# Sheet2.net
KiCad netlist of a schematic drawn in Altium Designer
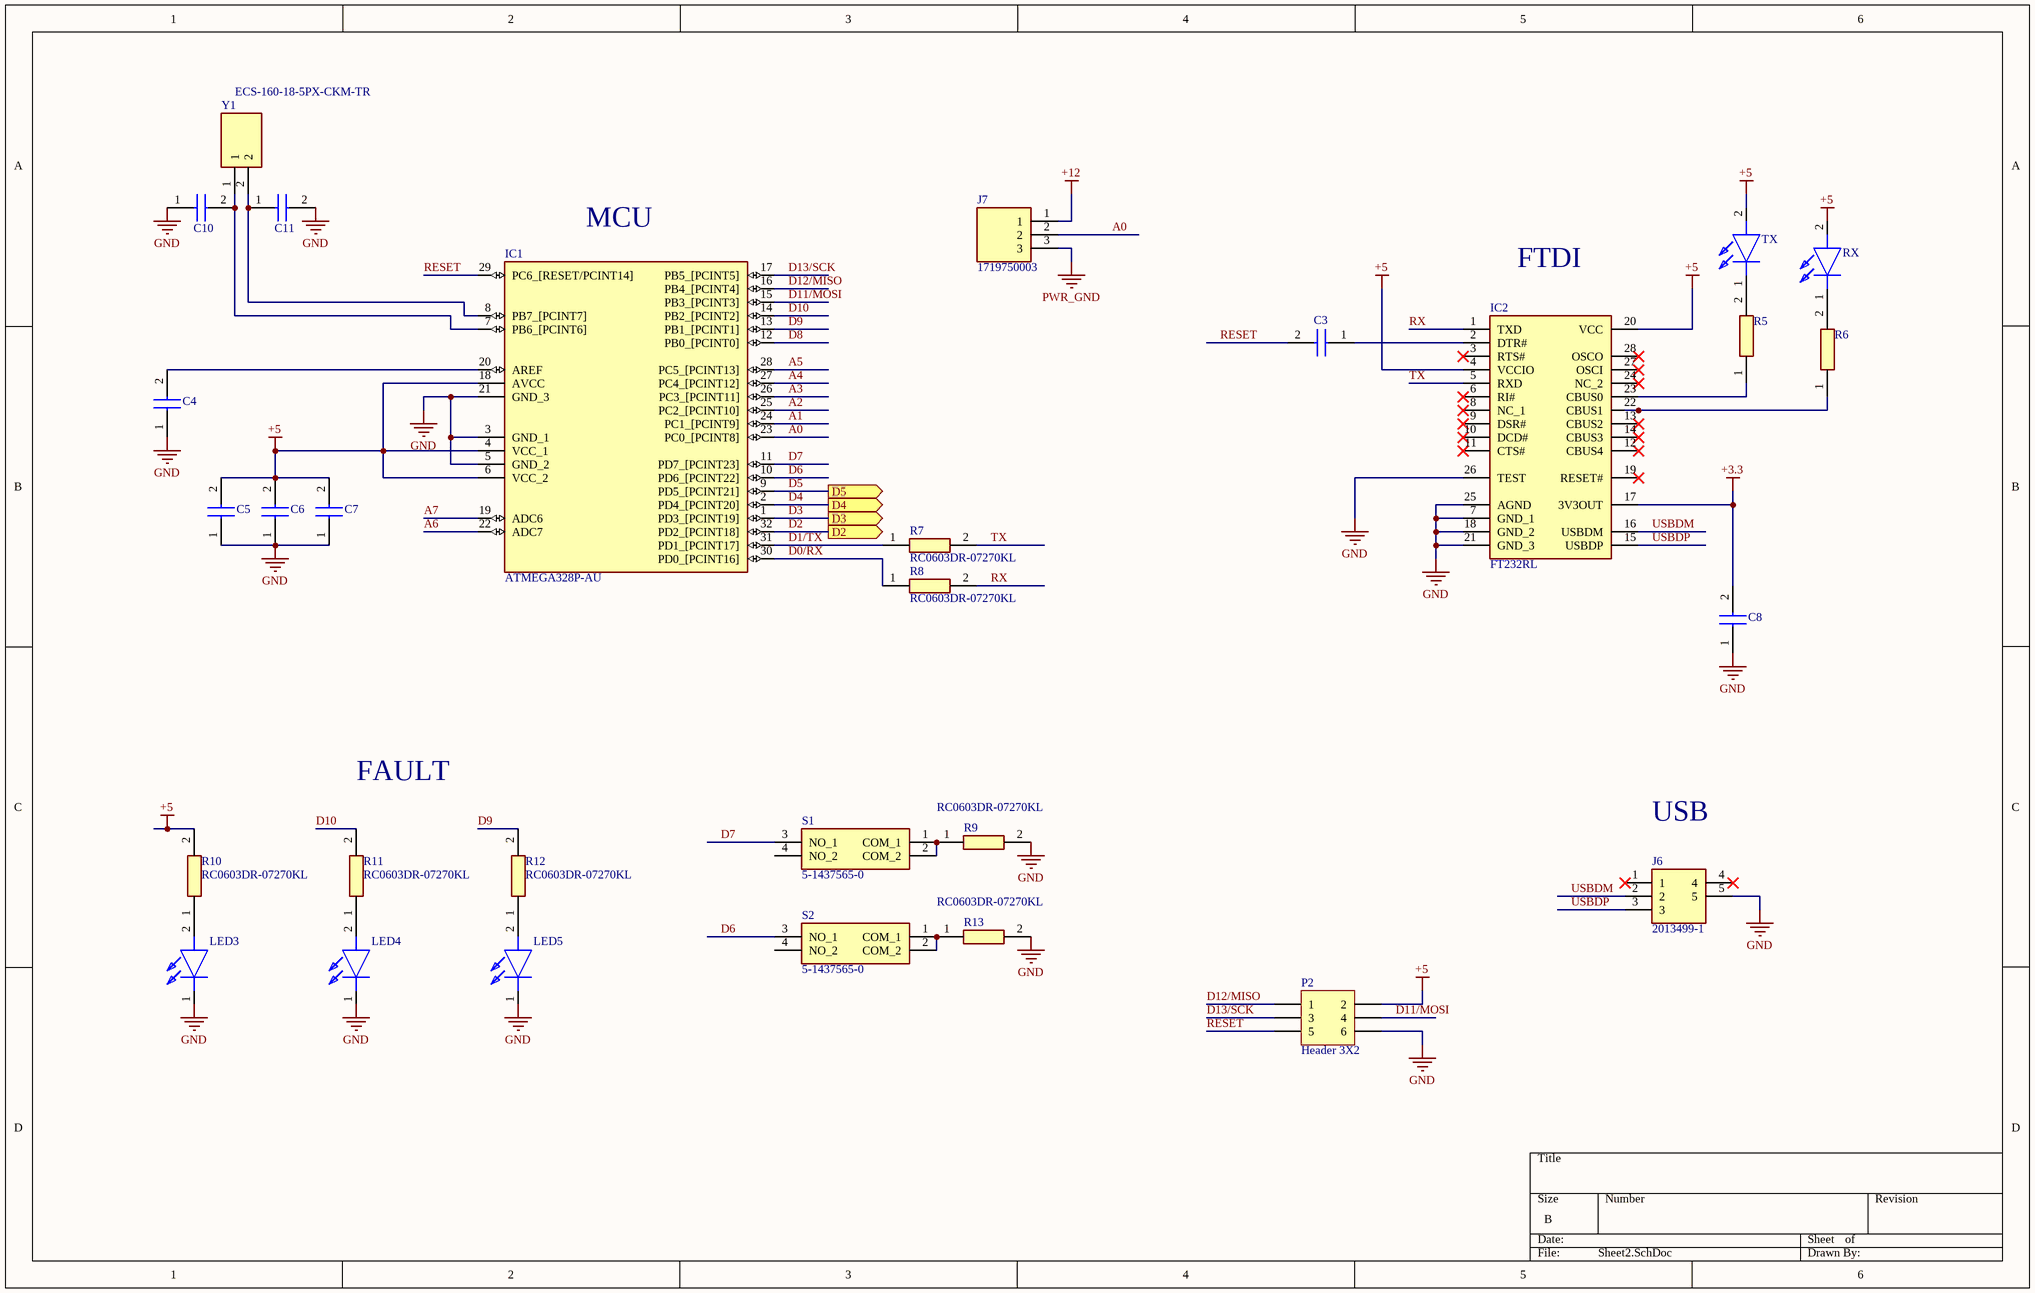
[diagram p0: Sheet2.SchDoc]

(export (version "E")
  (design (tool "Eeschema 10.0.6"))
  (components
    (comp (ref "C3")
      (value "C0603C104K3RACTU")
      (footprint "SamacSys:CAPC1608X95N")
      (description "Capacitor")
      (fields (field (name "MOUSER PART NUMBER") "80-C0603C104K3R"))
      (libsource (lib "PCB_Project") (part "C0603C104K3RACTU"))
    )
    (comp (ref "C4")
      (value "C0603C104K3RACTU")
      (footprint "SamacSys:CAPC1608X95N")
      (description "Capacitor")
      (fields (field (name "MOUSER PART NUMBER") "80-C0603C104K3R"))
      (libsource (lib "PCB_Project") (part "C0603C104K3RACTU"))
    )
    (comp (ref "C5")
      (value "C0603C104K3RACTU")
      (footprint "SamacSys:CAPC1608X95N")
      (description "Capacitor")
      (fields (field (name "MOUSER PART NUMBER") "80-C0603C104K3R"))
      (libsource (lib "PCB_Project") (part "C0603C104K3RACTU"))
    )
    (comp (ref "C6")
      (value "C0603C104K3RACTU")
      (footprint "SamacSys:CAPC1608X95N")
      (description "Capacitor")
      (fields (field (name "MOUSER PART NUMBER") "80-C0603C104K3R"))
      (libsource (lib "PCB_Project") (part "C0603C104K3RACTU"))
    )
    (comp (ref "C7")
      (value "C0603C104K3RACTU")
      (footprint "SamacSys:CAPC1608X95N")
      (description "Capacitor")
      (fields (field (name "MOUSER PART NUMBER") "80-C0603C104K3R"))
      (libsource (lib "PCB_Project") (part "C0603C104K3RACTU"))
    )
    (comp (ref "C8")
      (value "C0603C104K3RACTU")
      (footprint "SamacSys:CAPC1608X95N")
      (description "Capacitor")
      (fields (field (name "MOUSER PART NUMBER") "80-C0603C104K3R"))
      (libsource (lib "PCB_Project") (part "C0603C104K3RACTU"))
    )
    (comp (ref "C10")
      (value "C0603C104K3RACTU")
      (footprint "CAPC1608X95N")
      (description "Capacitor 20pf")
      (fields (field (name "MOUSER PART NUMBER") "80-C0603C104K3R"))
      (libsource (lib "PCB_Project") (part "06035A200KAT2A"))
    )
    (comp (ref "C11")
      (value "C0603C104K3RACTU")
      (footprint "CAPC1608X95N")
      (description "Capacitor 20pf")
      (fields (field (name "MOUSER PART NUMBER") "80-C0603C104K3R"))
      (libsource (lib "PCB_Project") (part "06035A200KAT2A"))
    )
    (comp (ref "IC1")
      (value "ATMEGA328P-AU")
      (footprint "SamacSys:QFP80P900X900X120-32N")
      (description "Integrated Circuit")
      (fields (field (name "MOUSER PART NUMBER") "556-ATMEGA328P-AU"))
      (libsource (lib "PCB_Project") (part "ATMEGA328P-AU"))
    )
    (comp (ref "IC2")
      (value "FT232RL")
      (footprint "SamacSys:SOP65P778X200-28N")
      (description "Integrated Circuit")
      (libsource (lib "PCB_Project") (part "FT232RL"))
    )
    (comp (ref "J6")
      (value "2013499-1")
      (footprint "SamacSys:2013499-1")
      (description "Connector")
      (fields (field (name "MOUSER PART NUMBER") "571-2013499-1"))
      (libsource (lib "*") (part "2013499-1"))
    )
    (comp (ref "J7")
      (value "1719750003")
      (footprint "171975YY03")
      (description "Connector")
      (libsource (lib "PCB_Project") (part "1719750003"))
    )
    (comp (ref "LED3")
      (value "LTST-C191TBKT-5A")
      (footprint "SamacSys:LEDC1608X65N")
      (description "LED")
      (fields (field (name "MOUSER PART NUMBER") "859-LTST-C191TBKT-5A"))
      (libsource (lib "*") (part "LTST-C191TBKT-5A"))
    )
    (comp (ref "LED4")
      (value "LTST-C191TBKT-5A")
      (footprint "SamacSys:LEDC1608X65N")
      (description "LED")
      (fields (field (name "MOUSER PART NUMBER") "859-LTST-C191TBKT-5A"))
      (libsource (lib "*") (part "LTST-C191TBKT-5A"))
    )
    (comp (ref "LED5")
      (value "LTST-C191TBKT-5A")
      (footprint "SamacSys:LEDC1608X65N")
      (description "LED")
      (fields (field (name "MOUSER PART NUMBER") "859-LTST-C191TBKT-5A"))
      (libsource (lib "*") (part "LTST-C191TBKT-5A"))
    )
    (comp (ref "P2")
      (value "Header 3X2")
      (footprint "HDR2X3")
      (description "Header, 3-Pin, Dual row")
      (fields (field (name "PUBLISHER") "Altium Limited"))
      (libsource (lib "Miscellaneous Connectors") (part "Header 3X2"))
    )
    (comp (ref "R5")
      (value "RC0603DR-07270KL")
      (footprint "SamacSys:RESC1608X55N")
      (description "Resistor")
      (libsource (lib "PCB_Project") (part "RC0603DR-07270KL"))
    )
    (comp (ref "R6")
      (value "RC0603DR-07270KL")
      (footprint "SamacSys:RESC1608X55N")
      (description "Resistor")
      (libsource (lib "PCB_Project") (part "RC0603DR-07270KL"))
    )
    (comp (ref "R7")
      (value "RC0603DR-07270KL")
      (footprint "SamacSys:RESC1608X55N")
      (description "Resistor")
      (libsource (lib "") (part "RC0603DR-07270KL_1"))
    )
    (comp (ref "R8")
      (value "RC0603DR-07270KL")
      (footprint "SamacSys:RESC1608X55N")
      (description "Resistor")
      (libsource (lib "") (part "RC0603DR-07270KL_1"))
    )
    (comp (ref "R9")
      (value "RC0603DR-07270KL")
      (footprint "SamacSys:RESC1608X55N")
      (description "Resistor")
      (libsource (lib "") (part "RC0603DR-07270KL_1"))
    )
    (comp (ref "R10")
      (value "RC0603DR-07270KL")
      (footprint "SamacSys:RESC1608X55N")
      (description "Resistor")
      (libsource (lib "PCB_Project") (part "RC0603DR-07270KL"))
    )
    (comp (ref "R11")
      (value "RC0603DR-07270KL")
      (footprint "SamacSys:RESC1608X55N")
      (description "Resistor")
      (libsource (lib "PCB_Project") (part "RC0603DR-07270KL"))
    )
    (comp (ref "R12")
      (value "RC0603DR-07270KL")
      (footprint "SamacSys:RESC1608X55N")
      (description "Resistor")
      (libsource (lib "PCB_Project") (part "RC0603DR-07270KL"))
    )
    (comp (ref "R13")
      (value "RC0603DR-07270KL")
      (footprint "SamacSys:RESC1608X55N")
      (description "Resistor")
      (libsource (lib "") (part "RC0603DR-07270KL_1"))
    )
    (comp (ref "RX")
      (value "LTST-C191TBKT-5A")
      (footprint "SamacSys:LEDC1608X65N")
      (description "LED")
      (fields (field (name "MOUSER PART NUMBER") "859-LTST-C191TBKT-5A"))
      (libsource (lib "*") (part "LTST-C191TBKT-5A"))
    )
    (comp (ref "S1")
      (value "5-1437565-0")
      (footprint "SamacSys:FSM6JSMATR")
      (description "Switch")
      (fields (field (name "MOUSER PART NUMBER") "506-5-1437565-0"))
      (libsource (lib "*") (part "5-1437565-0"))
    )
    (comp (ref "S2")
      (value "5-1437565-0")
      (footprint "SamacSys:FSM6JSMATR")
      (description "Switch")
      (fields (field (name "MOUSER PART NUMBER") "506-5-1437565-0"))
      (libsource (lib "*") (part "5-1437565-0"))
    )
    (comp (ref "TX")
      (value "LTST-C191TBKT-5A")
      (footprint "SamacSys:LEDC1608X65N")
      (description "LED")
      (fields (field (name "MOUSER PART NUMBER") "859-LTST-C191TBKT-5A"))
      (libsource (lib "*") (part "LTST-C191TBKT-5A"))
    )
    (comp (ref "Y1")
      (value "ECS-160-18-5PX-CKM-TR")
      (footprint "ECS49205PXTR")
      (description "Crystal or Oscillator")
      (libsource (lib "PCB_Project") (part "ECS-160-18-5PX-CKM-TR"))
    )
  )
  (nets
    (net (code "1") (name "+3.3") (class "Default")
      (node (ref "C8") (pin "2") (pinfunction "2_2") (pintype "passive"))
      (node (ref "IC2") (pin "17") (pinfunction "3V3OUT_17") (pintype "passive"))
    )
    (net (code "2") (name "+5") (class "Default")
      (node (ref "C5") (pin "2") (pinfunction "2_2") (pintype "passive"))
      (node (ref "C6") (pin "2") (pinfunction "2_2") (pintype "passive"))
      (node (ref "C7") (pin "2") (pinfunction "2_2") (pintype "passive"))
      (node (ref "IC1") (pin "18") (pinfunction "AVCC_18") (pintype "power_in"))
      (node (ref "IC1") (pin "4") (pinfunction "VCC_1_4") (pintype "power_in"))
      (node (ref "IC1") (pin "6") (pinfunction "VCC_2_6") (pintype "power_in"))
      (node (ref "IC2") (pin "20") (pinfunction "VCC_20") (pintype "passive"))
      (node (ref "IC2") (pin "4") (pinfunction "VCCIO_4") (pintype "passive"))
      (node (ref "P2") (pin "2") (pinfunction "2_2") (pintype "passive"))
      (node (ref "R10") (pin "2") (pinfunction "2_2") (pintype "passive"))
      (node (ref "RX") (pin "2") (pinfunction "A_2") (pintype "passive"))
      (node (ref "TX") (pin "2") (pinfunction "A_2") (pintype "passive"))
    )
    (net (code "3") (name "+12") (class "Default")
      (node (ref "J7") (pin "1") (pinfunction "1_1") (pintype "passive"))
    )
    (net (code "4") (name "/A0") (class "Default")
      (node (ref "IC1") (pin "23") (pinfunction "PC0_[PCINT8]_23") (pintype "bidirectional"))
      (node (ref "J7") (pin "2") (pinfunction "2_2") (pintype "passive"))
    )
    (net (code "5") (name "/A1") (class "Default")
      (node (ref "IC1") (pin "24") (pinfunction "PC1_[PCINT9]_24") (pintype "bidirectional"))
    )
    (net (code "6") (name "/A2") (class "Default")
      (node (ref "IC1") (pin "25") (pinfunction "PC2_[PCINT10]_25") (pintype "bidirectional"))
    )
    (net (code "7") (name "/A3") (class "Default")
      (node (ref "IC1") (pin "26") (pinfunction "PC3_[PCINT11]_26") (pintype "bidirectional"))
    )
    (net (code "8") (name "/A4") (class "Default")
      (node (ref "IC1") (pin "27") (pinfunction "PC4_[PCINT12]_27") (pintype "bidirectional"))
    )
    (net (code "9") (name "/A5") (class "Default")
      (node (ref "IC1") (pin "28") (pinfunction "PC5_[PCINT13]_28") (pintype "bidirectional"))
    )
    (net (code "10") (name "/A6") (class "Default")
      (node (ref "IC1") (pin "22") (pinfunction "ADC7_22") (pintype "bidirectional"))
    )
    (net (code "11") (name "/A7") (class "Default")
      (node (ref "IC1") (pin "19") (pinfunction "ADC6_19") (pintype "bidirectional"))
    )
    (net (code "12") (name "/D0{slash}RX") (class "Default")
      (node (ref "IC1") (pin "30") (pinfunction "PD0_[PCINT16]_30") (pintype "bidirectional"))
      (node (ref "R8") (pin "1") (pinfunction "1_1") (pintype "passive"))
    )
    (net (code "13") (name "/D1{slash}TX") (class "Default")
      (node (ref "IC1") (pin "31") (pinfunction "PD1_[PCINT17]_31") (pintype "bidirectional"))
      (node (ref "R7") (pin "1") (pinfunction "1_1") (pintype "passive"))
    )
    (net (code "14") (name "/D2") (class "Default")
      (node (ref "IC1") (pin "32") (pinfunction "PD2_[PCINT18]_32") (pintype "bidirectional"))
    )
    (net (code "15") (name "/D3") (class "Default")
      (node (ref "IC1") (pin "1") (pinfunction "PD3_[PCINT19]_1") (pintype "bidirectional"))
    )
    (net (code "16") (name "/D4") (class "Default")
      (node (ref "IC1") (pin "2") (pinfunction "PD4_[PCINT20]_2") (pintype "bidirectional"))
    )
    (net (code "17") (name "/D5") (class "Default")
      (node (ref "IC1") (pin "9") (pinfunction "PD5_[PCINT21]_9") (pintype "bidirectional"))
    )
    (net (code "18") (name "/D6") (class "Default")
      (node (ref "IC1") (pin "10") (pinfunction "PD6_[PCINT22]_10") (pintype "bidirectional"))
      (node (ref "S2") (pin "3") (pinfunction "NO_1_3") (pintype "passive"))
    )
    (net (code "19") (name "/D7") (class "Default")
      (node (ref "IC1") (pin "11") (pinfunction "PD7_[PCINT23]_11") (pintype "bidirectional"))
      (node (ref "S1") (pin "3") (pinfunction "NO_1_3") (pintype "passive"))
    )
    (net (code "20") (name "/D8") (class "Default")
      (node (ref "IC1") (pin "12") (pinfunction "PB0_[PCINT0]_12") (pintype "bidirectional"))
    )
    (net (code "21") (name "/D9") (class "Default")
      (node (ref "IC1") (pin "13") (pinfunction "PB1_[PCINT1]_13") (pintype "bidirectional"))
      (node (ref "R12") (pin "2") (pinfunction "2_2") (pintype "passive"))
    )
    (net (code "22") (name "/D10") (class "Default")
      (node (ref "IC1") (pin "14") (pinfunction "PB2_[PCINT2]_14") (pintype "bidirectional"))
      (node (ref "R11") (pin "2") (pinfunction "2_2") (pintype "passive"))
    )
    (net (code "23") (name "/D11{slash}MOSI") (class "Default")
      (node (ref "IC1") (pin "15") (pinfunction "PB3_[PCINT3]_15") (pintype "bidirectional"))
      (node (ref "P2") (pin "4") (pinfunction "4_4") (pintype "passive"))
    )
    (net (code "24") (name "/D12{slash}MISO") (class "Default")
      (node (ref "IC1") (pin "16") (pinfunction "PB4_[PCINT4]_16") (pintype "bidirectional"))
      (node (ref "P2") (pin "1") (pinfunction "1_1") (pintype "passive"))
    )
    (net (code "25") (name "/D13{slash}SCK") (class "Default")
      (node (ref "IC1") (pin "17") (pinfunction "PB5_[PCINT5]_17") (pintype "bidirectional"))
      (node (ref "P2") (pin "3") (pinfunction "3_3") (pintype "passive"))
    )
    (net (code "26") (name "/RESET") (class "Default")
      (node (ref "C3") (pin "2") (pinfunction "2_2") (pintype "passive"))
      (node (ref "IC1") (pin "29") (pinfunction "PC6_[RESET/PCINT14]_29") (pintype "bidirectional"))
      (node (ref "P2") (pin "5") (pinfunction "5_5") (pintype "passive"))
    )
    (net (code "27") (name "/RX") (class "Default")
      (node (ref "IC2") (pin "1") (pinfunction "TXD_1") (pintype "passive"))
      (node (ref "R8") (pin "2") (pinfunction "2_2") (pintype "passive"))
    )
    (net (code "28") (name "/TX") (class "Default")
      (node (ref "IC2") (pin "5") (pinfunction "RXD_5") (pintype "passive"))
      (node (ref "R7") (pin "2") (pinfunction "2_2") (pintype "passive"))
    )
    (net (code "29") (name "/USBDM") (class "Default")
      (node (ref "IC2") (pin "16") (pinfunction "USBDM_16") (pintype "passive"))
      (node (ref "J6") (pin "2") (pinfunction "2_2") (pintype "passive"))
    )
    (net (code "30") (name "/USBDP") (class "Default")
      (node (ref "IC2") (pin "15") (pinfunction "USBDP_15") (pintype "passive"))
      (node (ref "J6") (pin "3") (pinfunction "3_3") (pintype "passive"))
    )
    (net (code "31") (name "GND") (class "Default")
      (node (ref "C10") (pin "1") (pinfunction "1_1") (pintype "passive"))
      (node (ref "C11") (pin "2") (pinfunction "2_2") (pintype "passive"))
      (node (ref "C4") (pin "1") (pinfunction "1_1") (pintype "passive"))
      (node (ref "C5") (pin "1") (pinfunction "1_1") (pintype "passive"))
      (node (ref "C6") (pin "1") (pinfunction "1_1") (pintype "passive"))
      (node (ref "C7") (pin "1") (pinfunction "1_1") (pintype "passive"))
      (node (ref "C8") (pin "1") (pinfunction "1_1") (pintype "passive"))
      (node (ref "IC1") (pin "21") (pinfunction "GND_3_21") (pintype "power_in"))
      (node (ref "IC1") (pin "3") (pinfunction "GND_1_3") (pintype "power_in"))
      (node (ref "IC1") (pin "5") (pinfunction "GND_2_5") (pintype "power_in"))
      (node (ref "IC2") (pin "18") (pinfunction "GND_2_18") (pintype "passive"))
      (node (ref "IC2") (pin "21") (pinfunction "GND_3_21") (pintype "passive"))
      (node (ref "IC2") (pin "25") (pinfunction "AGND_25") (pintype "passive"))
      (node (ref "IC2") (pin "26") (pinfunction "TEST_26") (pintype "passive"))
      (node (ref "IC2") (pin "7") (pinfunction "GND_1_7") (pintype "passive"))
      (node (ref "J6") (pin "5") (pinfunction "5_5") (pintype "passive"))
      (node (ref "LED3") (pin "1") (pinfunction "K_1") (pintype "passive"))
      (node (ref "LED4") (pin "1") (pinfunction "K_1") (pintype "passive"))
      (node (ref "LED5") (pin "1") (pinfunction "K_1") (pintype "passive"))
      (node (ref "P2") (pin "6") (pinfunction "6_6") (pintype "passive"))
      (node (ref "R13") (pin "2") (pinfunction "2_2") (pintype "passive"))
      (node (ref "R9") (pin "2") (pinfunction "2_2") (pintype "passive"))
    )
    (net (code "32") (name "Net-(IC1-AREF)") (class "Default")
      (node (ref "C4") (pin "2") (pinfunction "2_2") (pintype "passive"))
      (node (ref "IC1") (pin "20") (pinfunction "AREF_20") (pintype "bidirectional"))
    )
    (net (code "33") (name "Net-(IC1-PB6_[PCINT6])") (class "Default")
      (node (ref "C10") (pin "2") (pinfunction "2_2") (pintype "passive"))
      (node (ref "IC1") (pin "7") (pinfunction "PB6_[PCINT6]_7") (pintype "bidirectional"))
      (node (ref "Y1") (pin "1") (pinfunction "1_1") (pintype "passive"))
    )
    (net (code "34") (name "Net-(IC1-PB7_[PCINT7])") (class "Default")
      (node (ref "C11") (pin "1") (pinfunction "1_1") (pintype "passive"))
      (node (ref "IC1") (pin "8") (pinfunction "PB7_[PCINT7]_8") (pintype "bidirectional"))
      (node (ref "Y1") (pin "2") (pinfunction "2_2") (pintype "passive"))
    )
    (net (code "35") (name "Net-(IC2-CBUS0)") (class "Default")
      (node (ref "IC2") (pin "23") (pinfunction "CBUS0_23") (pintype "passive"))
      (node (ref "R5") (pin "1") (pinfunction "1_1") (pintype "passive"))
    )
    (net (code "36") (name "Net-(IC2-CBUS1)") (class "Default")
      (node (ref "IC2") (pin "22") (pinfunction "CBUS1_22") (pintype "passive"))
      (node (ref "R6") (pin "1") (pinfunction "1_1") (pintype "passive"))
    )
    (net (code "37") (name "Net-(IC2-DTR#)") (class "Default")
      (node (ref "C3") (pin "1") (pinfunction "1_1") (pintype "passive"))
      (node (ref "IC2") (pin "2") (pinfunction "DTR#_2") (pintype "passive"))
    )
    (net (code "38") (name "Net-(LED3-A)") (class "Default")
      (node (ref "LED3") (pin "2") (pinfunction "A_2") (pintype "passive"))
      (node (ref "R10") (pin "1") (pinfunction "1_1") (pintype "passive"))
    )
    (net (code "39") (name "Net-(LED4-A)") (class "Default")
      (node (ref "LED4") (pin "2") (pinfunction "A_2") (pintype "passive"))
      (node (ref "R11") (pin "1") (pinfunction "1_1") (pintype "passive"))
    )
    (net (code "40") (name "Net-(LED5-A)") (class "Default")
      (node (ref "LED5") (pin "2") (pinfunction "A_2") (pintype "passive"))
      (node (ref "R12") (pin "1") (pinfunction "1_1") (pintype "passive"))
    )
    (net (code "41") (name "Net-(RX-K)") (class "Default")
      (node (ref "R6") (pin "2") (pinfunction "2_2") (pintype "passive"))
      (node (ref "RX") (pin "1") (pinfunction "K_1") (pintype "passive"))
    )
    (net (code "42") (name "Net-(S1-COM_1)") (class "Default")
      (node (ref "R9") (pin "1") (pinfunction "1_1") (pintype "passive"))
      (node (ref "S1") (pin "1") (pinfunction "COM_1_1") (pintype "passive"))
      (node (ref "S1") (pin "2") (pinfunction "COM_2_2") (pintype "passive"))
    )
    (net (code "43") (name "Net-(S2-COM_1)") (class "Default")
      (node (ref "R13") (pin "1") (pinfunction "1_1") (pintype "passive"))
      (node (ref "S2") (pin "1") (pinfunction "COM_1_1") (pintype "passive"))
      (node (ref "S2") (pin "2") (pinfunction "COM_2_2") (pintype "passive"))
    )
    (net (code "44") (name "Net-(TX-K)") (class "Default")
      (node (ref "R5") (pin "2") (pinfunction "2_2") (pintype "passive"))
      (node (ref "TX") (pin "1") (pinfunction "K_1") (pintype "passive"))
    )
    (net (code "45") (name "PWR_GND") (class "Default")
      (node (ref "J7") (pin "3") (pinfunction "3_3") (pintype "passive"))
    )
    (net (code "46") (name "unconnected-(IC2-CBUS2-Pad13)") (class "Default")
      (node (ref "IC2") (pin "13") (pinfunction "CBUS2_13") (pintype "passive+no_connect"))
    )
    (net (code "47") (name "unconnected-(IC2-CBUS3-Pad14)") (class "Default")
      (node (ref "IC2") (pin "14") (pinfunction "CBUS3_14") (pintype "passive+no_connect"))
    )
    (net (code "48") (name "unconnected-(IC2-CBUS4-Pad12)") (class "Default")
      (node (ref "IC2") (pin "12") (pinfunction "CBUS4_12") (pintype "passive+no_connect"))
    )
    (net (code "49") (name "unconnected-(IC2-CTS#-Pad11)") (class "Default")
      (node (ref "IC2") (pin "11") (pinfunction "CTS#_11") (pintype "passive+no_connect"))
    )
    (net (code "50") (name "unconnected-(IC2-DCD#-Pad10)") (class "Default")
      (node (ref "IC2") (pin "10") (pinfunction "DCD#_10") (pintype "passive+no_connect"))
    )
    (net (code "51") (name "unconnected-(IC2-DSR#-Pad9)") (class "Default")
      (node (ref "IC2") (pin "9") (pinfunction "DSR#_9") (pintype "passive+no_connect"))
    )
    (net (code "52") (name "unconnected-(IC2-NC_1-Pad8)") (class "Default")
      (node (ref "IC2") (pin "8") (pinfunction "NC_1_8") (pintype "passive+no_connect"))
    )
    (net (code "53") (name "unconnected-(IC2-NC_2-Pad24)") (class "Default")
      (node (ref "IC2") (pin "24") (pinfunction "NC_2_24") (pintype "passive+no_connect"))
    )
    (net (code "54") (name "unconnected-(IC2-OSCI-Pad27)") (class "Default")
      (node (ref "IC2") (pin "27") (pinfunction "OSCI_27") (pintype "passive+no_connect"))
    )
    (net (code "55") (name "unconnected-(IC2-OSCO-Pad28)") (class "Default")
      (node (ref "IC2") (pin "28") (pinfunction "OSCO_28") (pintype "passive+no_connect"))
    )
    (net (code "56") (name "unconnected-(IC2-RESET#-Pad19)") (class "Default")
      (node (ref "IC2") (pin "19") (pinfunction "RESET#_19") (pintype "passive+no_connect"))
    )
    (net (code "57") (name "unconnected-(IC2-RI#-Pad6)") (class "Default")
      (node (ref "IC2") (pin "6") (pinfunction "RI#_6") (pintype "passive+no_connect"))
    )
    (net (code "58") (name "unconnected-(IC2-RTS#-Pad3)") (class "Default")
      (node (ref "IC2") (pin "3") (pinfunction "RTS#_3") (pintype "passive+no_connect"))
    )
    (net (code "59") (name "unconnected-(J6-Pad1)") (class "Default")
      (node (ref "J6") (pin "1") (pinfunction "1_1") (pintype "passive+no_connect"))
    )
    (net (code "60") (name "unconnected-(J6-Pad4)") (class "Default")
      (node (ref "J6") (pin "4") (pinfunction "4_4") (pintype "passive+no_connect"))
    )
    (net (code "61") (name "unconnected-(S1-NO_2-Pad4)") (class "Default")
      (node (ref "S1") (pin "4") (pinfunction "NO_2_4") (pintype "passive"))
    )
    (net (code "62") (name "unconnected-(S2-NO_2-Pad4)") (class "Default")
      (node (ref "S2") (pin "4") (pinfunction "NO_2_4") (pintype "passive"))
    )
  )
)
